# module_RevD.net
KiCad netlist of a schematic drawn in EAGLE
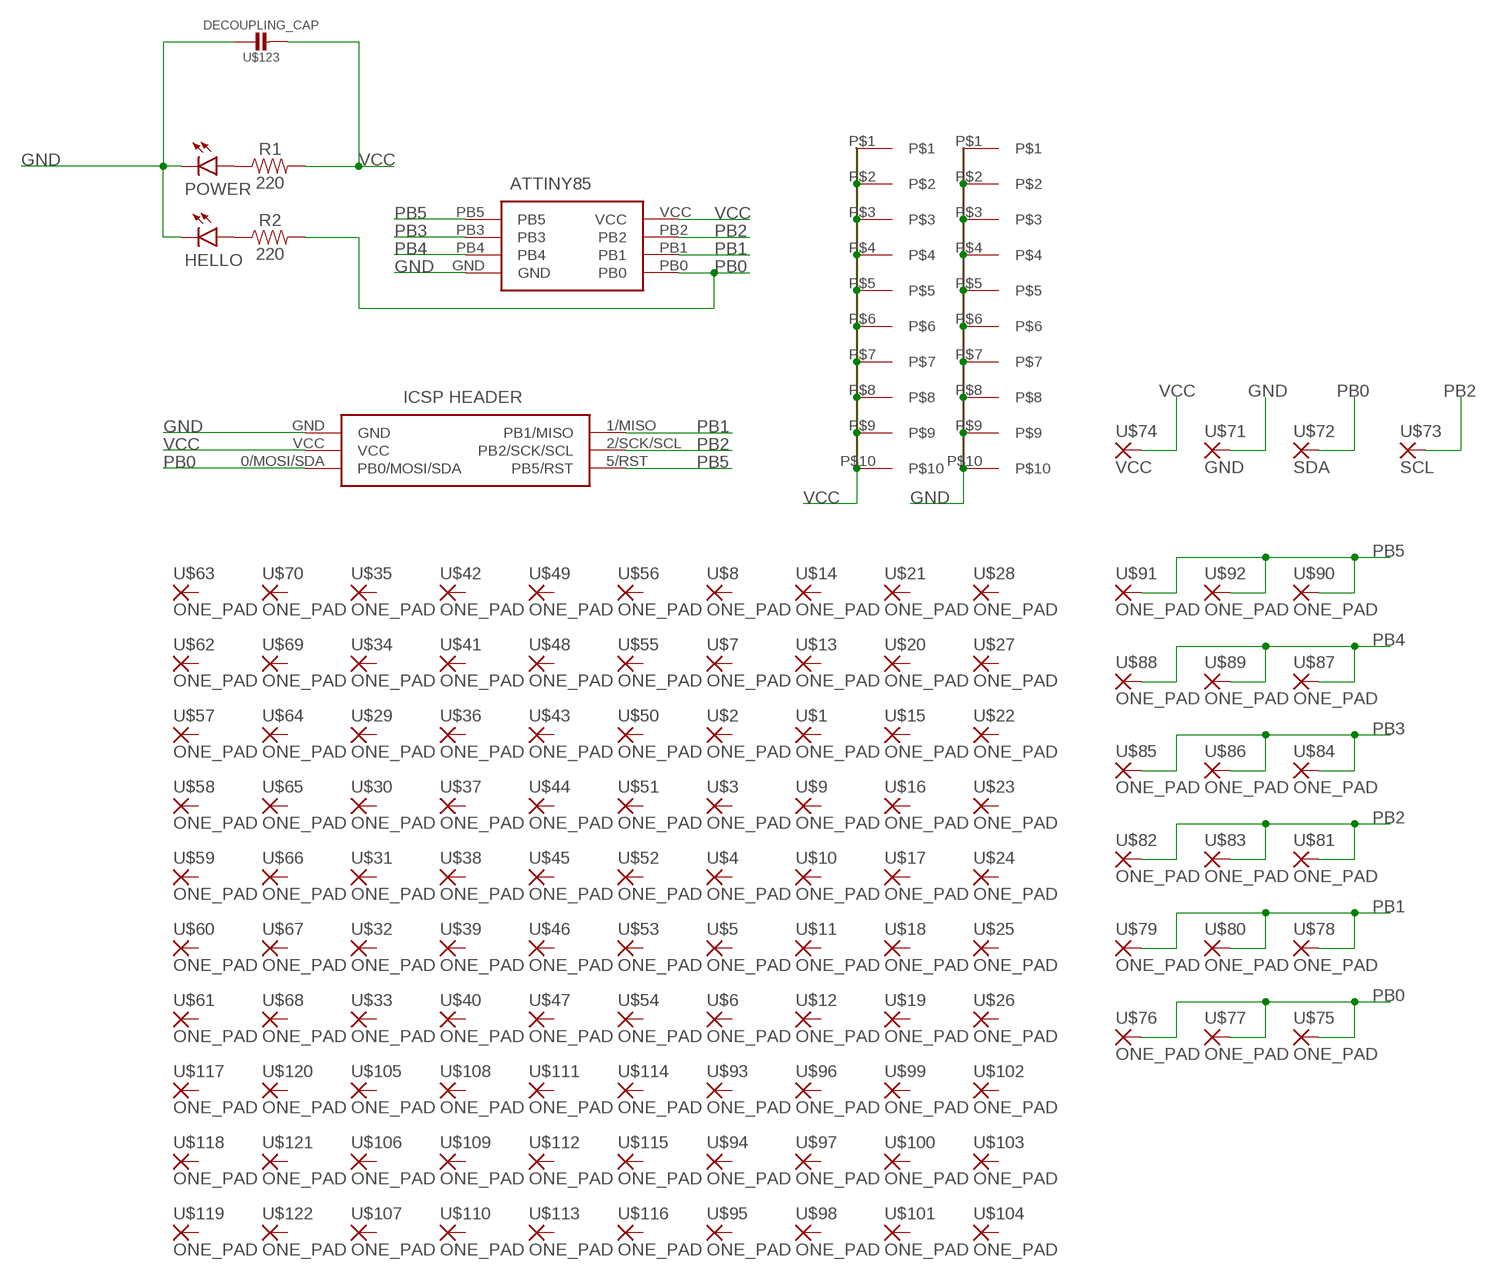
[diagram p0: schematic, sheet 1]

(export (version "E")
  (design (tool "Eeschema 10.0.6"))
  (components
    (comp (ref "GND")
      (value "10X-PADS")
      (footprint "eagle-import:10X-PADS")
      (libsource (lib "eagle-import") (part "10X-PADS"))
    )
    (comp (ref "HELLO")
      (value "LED3MM")
      (footprint "eagle-import:LED3MM")
      (libsource (lib "eagle-import") (part "LED3MM"))
    )
    (comp (ref "IC1")
      (value "ATTINY85-20SU")
      (footprint "eagle-import:SOT127P798X216-8N")
      (fields (field (name "RS_PART_NUMBER") "1331674"))
      (libsource (lib "eagle-import") (part "ATTINY85-20SU"))
    )
    (comp (ref "J1")
      (value "M20-9980346")
      (footprint "eagle-import:HDRV6W64P254_2X3_762X508X868P")
      (fields (field (name "RS_PART_NUMBER") "7457046P"))
      (libsource (lib "eagle-import") (part "M20-9980346"))
    )
    (comp (ref "POWER")
      (value "LED3MM")
      (footprint "eagle-import:LED3MM")
      (libsource (lib "eagle-import") (part "LED3MM"))
    )
    (comp (ref "R1")
      (value "220")
      (footprint "eagle-import:AXIAL-0.3")
      (libsource (lib "eagle-import") (part "RESISTORAXIAL-0.3"))
    )
    (comp (ref "R2")
      (value "220")
      (footprint "eagle-import:AXIAL-0.3")
      (libsource (lib "eagle-import") (part "RESISTORAXIAL-0.3"))
    )
    (comp (ref "U$1")
      (value "ONE_PAD")
      (footprint "eagle-import:1X01")
      (libsource (lib "eagle-import") (part "ONE_PAD"))
    )
    (comp (ref "U$2")
      (value "ONE_PAD")
      (footprint "eagle-import:1X01")
      (libsource (lib "eagle-import") (part "ONE_PAD"))
    )
    (comp (ref "U$3")
      (value "ONE_PAD")
      (footprint "eagle-import:1X01")
      (libsource (lib "eagle-import") (part "ONE_PAD"))
    )
    (comp (ref "U$4")
      (value "ONE_PAD")
      (footprint "eagle-import:1X01")
      (libsource (lib "eagle-import") (part "ONE_PAD"))
    )
    (comp (ref "U$5")
      (value "ONE_PAD")
      (footprint "eagle-import:1X01")
      (libsource (lib "eagle-import") (part "ONE_PAD"))
    )
    (comp (ref "U$6")
      (value "ONE_PAD")
      (footprint "eagle-import:1X01")
      (libsource (lib "eagle-import") (part "ONE_PAD"))
    )
    (comp (ref "U$7")
      (value "ONE_PAD")
      (footprint "eagle-import:1X01")
      (libsource (lib "eagle-import") (part "ONE_PAD"))
    )
    (comp (ref "U$8")
      (value "ONE_PAD")
      (footprint "eagle-import:1X01")
      (libsource (lib "eagle-import") (part "ONE_PAD"))
    )
    (comp (ref "U$9")
      (value "ONE_PAD")
      (footprint "eagle-import:1X01")
      (libsource (lib "eagle-import") (part "ONE_PAD"))
    )
    (comp (ref "U$10")
      (value "ONE_PAD")
      (footprint "eagle-import:1X01")
      (libsource (lib "eagle-import") (part "ONE_PAD"))
    )
    (comp (ref "U$11")
      (value "ONE_PAD")
      (footprint "eagle-import:1X01")
      (libsource (lib "eagle-import") (part "ONE_PAD"))
    )
    (comp (ref "U$12")
      (value "ONE_PAD")
      (footprint "eagle-import:1X01")
      (libsource (lib "eagle-import") (part "ONE_PAD"))
    )
    (comp (ref "U$13")
      (value "ONE_PAD")
      (footprint "eagle-import:1X01")
      (libsource (lib "eagle-import") (part "ONE_PAD"))
    )
    (comp (ref "U$14")
      (value "ONE_PAD")
      (footprint "eagle-import:1X01")
      (libsource (lib "eagle-import") (part "ONE_PAD"))
    )
    (comp (ref "U$15")
      (value "ONE_PAD")
      (footprint "eagle-import:1X01")
      (libsource (lib "eagle-import") (part "ONE_PAD"))
    )
    (comp (ref "U$16")
      (value "ONE_PAD")
      (footprint "eagle-import:1X01")
      (libsource (lib "eagle-import") (part "ONE_PAD"))
    )
    (comp (ref "U$17")
      (value "ONE_PAD")
      (footprint "eagle-import:1X01")
      (libsource (lib "eagle-import") (part "ONE_PAD"))
    )
    (comp (ref "U$18")
      (value "ONE_PAD")
      (footprint "eagle-import:1X01")
      (libsource (lib "eagle-import") (part "ONE_PAD"))
    )
    (comp (ref "U$19")
      (value "ONE_PAD")
      (footprint "eagle-import:1X01")
      (libsource (lib "eagle-import") (part "ONE_PAD"))
    )
    (comp (ref "U$20")
      (value "ONE_PAD")
      (footprint "eagle-import:1X01")
      (libsource (lib "eagle-import") (part "ONE_PAD"))
    )
    (comp (ref "U$21")
      (value "ONE_PAD")
      (footprint "eagle-import:1X01")
      (libsource (lib "eagle-import") (part "ONE_PAD"))
    )
    (comp (ref "U$22")
      (value "ONE_PAD")
      (footprint "eagle-import:1X01")
      (libsource (lib "eagle-import") (part "ONE_PAD"))
    )
    (comp (ref "U$23")
      (value "ONE_PAD")
      (footprint "eagle-import:1X01")
      (libsource (lib "eagle-import") (part "ONE_PAD"))
    )
    (comp (ref "U$24")
      (value "ONE_PAD")
      (footprint "eagle-import:1X01")
      (libsource (lib "eagle-import") (part "ONE_PAD"))
    )
    (comp (ref "U$25")
      (value "ONE_PAD")
      (footprint "eagle-import:1X01")
      (libsource (lib "eagle-import") (part "ONE_PAD"))
    )
    (comp (ref "U$26")
      (value "ONE_PAD")
      (footprint "eagle-import:1X01")
      (libsource (lib "eagle-import") (part "ONE_PAD"))
    )
    (comp (ref "U$27")
      (value "ONE_PAD")
      (footprint "eagle-import:1X01")
      (libsource (lib "eagle-import") (part "ONE_PAD"))
    )
    (comp (ref "U$28")
      (value "ONE_PAD")
      (footprint "eagle-import:1X01")
      (libsource (lib "eagle-import") (part "ONE_PAD"))
    )
    (comp (ref "U$29")
      (value "ONE_PAD")
      (footprint "eagle-import:1X01")
      (libsource (lib "eagle-import") (part "ONE_PAD"))
    )
    (comp (ref "U$30")
      (value "ONE_PAD")
      (footprint "eagle-import:1X01")
      (libsource (lib "eagle-import") (part "ONE_PAD"))
    )
    (comp (ref "U$31")
      (value "ONE_PAD")
      (footprint "eagle-import:1X01")
      (libsource (lib "eagle-import") (part "ONE_PAD"))
    )
    (comp (ref "U$32")
      (value "ONE_PAD")
      (footprint "eagle-import:1X01")
      (libsource (lib "eagle-import") (part "ONE_PAD"))
    )
    (comp (ref "U$33")
      (value "ONE_PAD")
      (footprint "eagle-import:1X01")
      (libsource (lib "eagle-import") (part "ONE_PAD"))
    )
    (comp (ref "U$34")
      (value "ONE_PAD")
      (footprint "eagle-import:1X01")
      (libsource (lib "eagle-import") (part "ONE_PAD"))
    )
    (comp (ref "U$35")
      (value "ONE_PAD")
      (footprint "eagle-import:1X01")
      (libsource (lib "eagle-import") (part "ONE_PAD"))
    )
    (comp (ref "U$36")
      (value "ONE_PAD")
      (footprint "eagle-import:1X01")
      (libsource (lib "eagle-import") (part "ONE_PAD"))
    )
    (comp (ref "U$37")
      (value "ONE_PAD")
      (footprint "eagle-import:1X01")
      (libsource (lib "eagle-import") (part "ONE_PAD"))
    )
    (comp (ref "U$38")
      (value "ONE_PAD")
      (footprint "eagle-import:1X01")
      (libsource (lib "eagle-import") (part "ONE_PAD"))
    )
    (comp (ref "U$39")
      (value "ONE_PAD")
      (footprint "eagle-import:1X01")
      (libsource (lib "eagle-import") (part "ONE_PAD"))
    )
    (comp (ref "U$40")
      (value "ONE_PAD")
      (footprint "eagle-import:1X01")
      (libsource (lib "eagle-import") (part "ONE_PAD"))
    )
    (comp (ref "U$41")
      (value "ONE_PAD")
      (footprint "eagle-import:1X01")
      (libsource (lib "eagle-import") (part "ONE_PAD"))
    )
    (comp (ref "U$42")
      (value "ONE_PAD")
      (footprint "eagle-import:1X01")
      (libsource (lib "eagle-import") (part "ONE_PAD"))
    )
    (comp (ref "U$43")
      (value "ONE_PAD")
      (footprint "eagle-import:1X01")
      (libsource (lib "eagle-import") (part "ONE_PAD"))
    )
    (comp (ref "U$44")
      (value "ONE_PAD")
      (footprint "eagle-import:1X01")
      (libsource (lib "eagle-import") (part "ONE_PAD"))
    )
    (comp (ref "U$45")
      (value "ONE_PAD")
      (footprint "eagle-import:1X01")
      (libsource (lib "eagle-import") (part "ONE_PAD"))
    )
    (comp (ref "U$46")
      (value "ONE_PAD")
      (footprint "eagle-import:1X01")
      (libsource (lib "eagle-import") (part "ONE_PAD"))
    )
    (comp (ref "U$47")
      (value "ONE_PAD")
      (footprint "eagle-import:1X01")
      (libsource (lib "eagle-import") (part "ONE_PAD"))
    )
    (comp (ref "U$48")
      (value "ONE_PAD")
      (footprint "eagle-import:1X01")
      (libsource (lib "eagle-import") (part "ONE_PAD"))
    )
    (comp (ref "U$49")
      (value "ONE_PAD")
      (footprint "eagle-import:1X01")
      (libsource (lib "eagle-import") (part "ONE_PAD"))
    )
    (comp (ref "U$50")
      (value "ONE_PAD")
      (footprint "eagle-import:1X01")
      (libsource (lib "eagle-import") (part "ONE_PAD"))
    )
    (comp (ref "U$51")
      (value "ONE_PAD")
      (footprint "eagle-import:1X01")
      (libsource (lib "eagle-import") (part "ONE_PAD"))
    )
    (comp (ref "U$52")
      (value "ONE_PAD")
      (footprint "eagle-import:1X01")
      (libsource (lib "eagle-import") (part "ONE_PAD"))
    )
    (comp (ref "U$53")
      (value "ONE_PAD")
      (footprint "eagle-import:1X01")
      (libsource (lib "eagle-import") (part "ONE_PAD"))
    )
    (comp (ref "U$54")
      (value "ONE_PAD")
      (footprint "eagle-import:1X01")
      (libsource (lib "eagle-import") (part "ONE_PAD"))
    )
    (comp (ref "U$55")
      (value "ONE_PAD")
      (footprint "eagle-import:1X01")
      (libsource (lib "eagle-import") (part "ONE_PAD"))
    )
    (comp (ref "U$56")
      (value "ONE_PAD")
      (footprint "eagle-import:1X01")
      (libsource (lib "eagle-import") (part "ONE_PAD"))
    )
    (comp (ref "U$57")
      (value "ONE_PAD")
      (footprint "eagle-import:1X01")
      (libsource (lib "eagle-import") (part "ONE_PAD"))
    )
    (comp (ref "U$58")
      (value "ONE_PAD")
      (footprint "eagle-import:1X01")
      (libsource (lib "eagle-import") (part "ONE_PAD"))
    )
    (comp (ref "U$59")
      (value "ONE_PAD")
      (footprint "eagle-import:1X01")
      (libsource (lib "eagle-import") (part "ONE_PAD"))
    )
    (comp (ref "U$60")
      (value "ONE_PAD")
      (footprint "eagle-import:1X01")
      (libsource (lib "eagle-import") (part "ONE_PAD"))
    )
    (comp (ref "U$61")
      (value "ONE_PAD")
      (footprint "eagle-import:1X01")
      (libsource (lib "eagle-import") (part "ONE_PAD"))
    )
    (comp (ref "U$62")
      (value "ONE_PAD")
      (footprint "eagle-import:1X01")
      (libsource (lib "eagle-import") (part "ONE_PAD"))
    )
    (comp (ref "U$63")
      (value "ONE_PAD")
      (footprint "eagle-import:1X01")
      (libsource (lib "eagle-import") (part "ONE_PAD"))
    )
    (comp (ref "U$64")
      (value "ONE_PAD")
      (footprint "eagle-import:1X01")
      (libsource (lib "eagle-import") (part "ONE_PAD"))
    )
    (comp (ref "U$65")
      (value "ONE_PAD")
      (footprint "eagle-import:1X01")
      (libsource (lib "eagle-import") (part "ONE_PAD"))
    )
    (comp (ref "U$66")
      (value "ONE_PAD")
      (footprint "eagle-import:1X01")
      (libsource (lib "eagle-import") (part "ONE_PAD"))
    )
    (comp (ref "U$67")
      (value "ONE_PAD")
      (footprint "eagle-import:1X01")
      (libsource (lib "eagle-import") (part "ONE_PAD"))
    )
    (comp (ref "U$68")
      (value "ONE_PAD")
      (footprint "eagle-import:1X01")
      (libsource (lib "eagle-import") (part "ONE_PAD"))
    )
    (comp (ref "U$69")
      (value "ONE_PAD")
      (footprint "eagle-import:1X01")
      (libsource (lib "eagle-import") (part "ONE_PAD"))
    )
    (comp (ref "U$70")
      (value "ONE_PAD")
      (footprint "eagle-import:1X01")
      (libsource (lib "eagle-import") (part "ONE_PAD"))
    )
    (comp (ref "U$71")
      (value "GND")
      (footprint "eagle-import:1X01")
      (libsource (lib "eagle-import") (part "ONE_PAD"))
    )
    (comp (ref "U$72")
      (value "SDA")
      (footprint "eagle-import:1X01")
      (libsource (lib "eagle-import") (part "ONE_PAD"))
    )
    (comp (ref "U$73")
      (value "SCL")
      (footprint "eagle-import:1X01")
      (libsource (lib "eagle-import") (part "ONE_PAD"))
    )
    (comp (ref "U$74")
      (value "VCC")
      (footprint "eagle-import:1X01")
      (libsource (lib "eagle-import") (part "ONE_PAD"))
    )
    (comp (ref "U$75")
      (value "ONE_PAD")
      (footprint "eagle-import:1X01")
      (libsource (lib "eagle-import") (part "ONE_PAD"))
    )
    (comp (ref "U$76")
      (value "ONE_PAD")
      (footprint "eagle-import:1X01")
      (libsource (lib "eagle-import") (part "ONE_PAD"))
    )
    (comp (ref "U$77")
      (value "ONE_PAD")
      (footprint "eagle-import:1X01")
      (libsource (lib "eagle-import") (part "ONE_PAD"))
    )
    (comp (ref "U$78")
      (value "ONE_PAD")
      (footprint "eagle-import:1X01")
      (libsource (lib "eagle-import") (part "ONE_PAD"))
    )
    (comp (ref "U$79")
      (value "ONE_PAD")
      (footprint "eagle-import:1X01")
      (libsource (lib "eagle-import") (part "ONE_PAD"))
    )
    (comp (ref "U$80")
      (value "ONE_PAD")
      (footprint "eagle-import:1X01")
      (libsource (lib "eagle-import") (part "ONE_PAD"))
    )
    (comp (ref "U$81")
      (value "ONE_PAD")
      (footprint "eagle-import:1X01")
      (libsource (lib "eagle-import") (part "ONE_PAD"))
    )
    (comp (ref "U$82")
      (value "ONE_PAD")
      (footprint "eagle-import:1X01")
      (libsource (lib "eagle-import") (part "ONE_PAD"))
    )
    (comp (ref "U$83")
      (value "ONE_PAD")
      (footprint "eagle-import:1X01")
      (libsource (lib "eagle-import") (part "ONE_PAD"))
    )
    (comp (ref "U$84")
      (value "ONE_PAD")
      (footprint "eagle-import:1X01")
      (libsource (lib "eagle-import") (part "ONE_PAD"))
    )
    (comp (ref "U$85")
      (value "ONE_PAD")
      (footprint "eagle-import:1X01")
      (libsource (lib "eagle-import") (part "ONE_PAD"))
    )
    (comp (ref "U$86")
      (value "ONE_PAD")
      (footprint "eagle-import:1X01")
      (libsource (lib "eagle-import") (part "ONE_PAD"))
    )
    (comp (ref "U$87")
      (value "ONE_PAD")
      (footprint "eagle-import:1X01")
      (libsource (lib "eagle-import") (part "ONE_PAD"))
    )
    (comp (ref "U$88")
      (value "ONE_PAD")
      (footprint "eagle-import:1X01")
      (libsource (lib "eagle-import") (part "ONE_PAD"))
    )
    (comp (ref "U$89")
      (value "ONE_PAD")
      (footprint "eagle-import:1X01")
      (libsource (lib "eagle-import") (part "ONE_PAD"))
    )
    (comp (ref "U$90")
      (value "ONE_PAD")
      (footprint "eagle-import:1X01")
      (libsource (lib "eagle-import") (part "ONE_PAD"))
    )
    (comp (ref "U$91")
      (value "ONE_PAD")
      (footprint "eagle-import:1X01")
      (libsource (lib "eagle-import") (part "ONE_PAD"))
    )
    (comp (ref "U$92")
      (value "ONE_PAD")
      (footprint "eagle-import:1X01")
      (libsource (lib "eagle-import") (part "ONE_PAD"))
    )
    (comp (ref "U$93")
      (value "ONE_PAD")
      (footprint "eagle-import:1X01")
      (libsource (lib "eagle-import") (part "ONE_PAD"))
    )
    (comp (ref "U$94")
      (value "ONE_PAD")
      (footprint "eagle-import:1X01")
      (libsource (lib "eagle-import") (part "ONE_PAD"))
    )
    (comp (ref "U$95")
      (value "ONE_PAD")
      (footprint "eagle-import:1X01")
      (libsource (lib "eagle-import") (part "ONE_PAD"))
    )
    (comp (ref "U$96")
      (value "ONE_PAD")
      (footprint "eagle-import:1X01")
      (libsource (lib "eagle-import") (part "ONE_PAD"))
    )
    (comp (ref "U$97")
      (value "ONE_PAD")
      (footprint "eagle-import:1X01")
      (libsource (lib "eagle-import") (part "ONE_PAD"))
    )
    (comp (ref "U$98")
      (value "ONE_PAD")
      (footprint "eagle-import:1X01")
      (libsource (lib "eagle-import") (part "ONE_PAD"))
    )
    (comp (ref "U$99")
      (value "ONE_PAD")
      (footprint "eagle-import:1X01")
      (libsource (lib "eagle-import") (part "ONE_PAD"))
    )
    (comp (ref "U$100")
      (value "ONE_PAD")
      (footprint "eagle-import:1X01")
      (libsource (lib "eagle-import") (part "ONE_PAD"))
    )
    (comp (ref "U$101")
      (value "ONE_PAD")
      (footprint "eagle-import:1X01")
      (libsource (lib "eagle-import") (part "ONE_PAD"))
    )
    (comp (ref "U$102")
      (value "ONE_PAD")
      (footprint "eagle-import:1X01")
      (libsource (lib "eagle-import") (part "ONE_PAD"))
    )
    (comp (ref "U$103")
      (value "ONE_PAD")
      (footprint "eagle-import:1X01")
      (libsource (lib "eagle-import") (part "ONE_PAD"))
    )
    (comp (ref "U$104")
      (value "ONE_PAD")
      (footprint "eagle-import:1X01")
      (libsource (lib "eagle-import") (part "ONE_PAD"))
    )
    (comp (ref "U$105")
      (value "ONE_PAD")
      (footprint "eagle-import:1X01")
      (libsource (lib "eagle-import") (part "ONE_PAD"))
    )
    (comp (ref "U$106")
      (value "ONE_PAD")
      (footprint "eagle-import:1X01")
      (libsource (lib "eagle-import") (part "ONE_PAD"))
    )
    (comp (ref "U$107")
      (value "ONE_PAD")
      (footprint "eagle-import:1X01")
      (libsource (lib "eagle-import") (part "ONE_PAD"))
    )
    (comp (ref "U$108")
      (value "ONE_PAD")
      (footprint "eagle-import:1X01")
      (libsource (lib "eagle-import") (part "ONE_PAD"))
    )
    (comp (ref "U$109")
      (value "ONE_PAD")
      (footprint "eagle-import:1X01")
      (libsource (lib "eagle-import") (part "ONE_PAD"))
    )
    (comp (ref "U$110")
      (value "ONE_PAD")
      (footprint "eagle-import:1X01")
      (libsource (lib "eagle-import") (part "ONE_PAD"))
    )
    (comp (ref "U$111")
      (value "ONE_PAD")
      (footprint "eagle-import:1X01")
      (libsource (lib "eagle-import") (part "ONE_PAD"))
    )
    (comp (ref "U$112")
      (value "ONE_PAD")
      (footprint "eagle-import:1X01")
      (libsource (lib "eagle-import") (part "ONE_PAD"))
    )
    (comp (ref "U$113")
      (value "ONE_PAD")
      (footprint "eagle-import:1X01")
      (libsource (lib "eagle-import") (part "ONE_PAD"))
    )
    (comp (ref "U$114")
      (value "ONE_PAD")
      (footprint "eagle-import:1X01")
      (libsource (lib "eagle-import") (part "ONE_PAD"))
    )
    (comp (ref "U$115")
      (value "ONE_PAD")
      (footprint "eagle-import:1X01")
      (libsource (lib "eagle-import") (part "ONE_PAD"))
    )
    (comp (ref "U$116")
      (value "ONE_PAD")
      (footprint "eagle-import:1X01")
      (libsource (lib "eagle-import") (part "ONE_PAD"))
    )
    (comp (ref "U$117")
      (value "ONE_PAD")
      (footprint "eagle-import:1X01")
      (libsource (lib "eagle-import") (part "ONE_PAD"))
    )
    (comp (ref "U$118")
      (value "ONE_PAD")
      (footprint "eagle-import:1X01")
      (libsource (lib "eagle-import") (part "ONE_PAD"))
    )
    (comp (ref "U$119")
      (value "ONE_PAD")
      (footprint "eagle-import:1X01")
      (libsource (lib "eagle-import") (part "ONE_PAD"))
    )
    (comp (ref "U$120")
      (value "ONE_PAD")
      (footprint "eagle-import:1X01")
      (libsource (lib "eagle-import") (part "ONE_PAD"))
    )
    (comp (ref "U$121")
      (value "ONE_PAD")
      (footprint "eagle-import:1X01")
      (libsource (lib "eagle-import") (part "ONE_PAD"))
    )
    (comp (ref "U$122")
      (value "ONE_PAD")
      (footprint "eagle-import:1X01")
      (libsource (lib "eagle-import") (part "ONE_PAD"))
    )
    (comp (ref "U$123")
      (value "DECOUPLING_CAP")
      (footprint "eagle-import:DECOUPLING_CAP")
      (libsource (lib "eagle-import") (part "DECOUPLING_CAP"))
    )
    (comp (ref "VCC")
      (value "10X-PADS")
      (footprint "eagle-import:10X-PADS")
      (libsource (lib "eagle-import") (part "10X-PADS"))
    )
  )
  (nets
    (net (code "1") (name "/GND") (class "Default")
      (node (ref "GND") (pin "P$1") (pinfunction "P$1_P$1") (pintype "bidirectional"))
      (node (ref "GND") (pin "P$10") (pinfunction "P$10_P$10") (pintype "bidirectional"))
      (node (ref "GND") (pin "P$2") (pinfunction "P$2_P$2") (pintype "bidirectional"))
      (node (ref "GND") (pin "P$3") (pinfunction "P$3_P$3") (pintype "bidirectional"))
      (node (ref "GND") (pin "P$4") (pinfunction "P$4_P$4") (pintype "bidirectional"))
      (node (ref "GND") (pin "P$5") (pinfunction "P$5_P$5") (pintype "bidirectional"))
      (node (ref "GND") (pin "P$6") (pinfunction "P$6_P$6") (pintype "bidirectional"))
      (node (ref "GND") (pin "P$7") (pinfunction "P$7_P$7") (pintype "bidirectional"))
      (node (ref "GND") (pin "P$8") (pinfunction "P$8_P$8") (pintype "bidirectional"))
      (node (ref "GND") (pin "P$9") (pinfunction "P$9_P$9") (pintype "bidirectional"))
      (node (ref "HELLO") (pin "NEG") (pinfunction "NEG_NEG") (pintype "passive"))
      (node (ref "IC1") (pin "GND") (pinfunction "GND_GND") (pintype "bidirectional"))
      (node (ref "J1") (pin "GND") (pinfunction "GND_GND") (pintype "bidirectional"))
      (node (ref "POWER") (pin "NEG") (pinfunction "NEG_NEG") (pintype "passive"))
      (node (ref "U$123") (pin "1") (pinfunction "1_1") (pintype "passive"))
      (node (ref "U$71") (pin "P$1") (pinfunction "P_P$1") (pintype "passive"))
    )
    (net (code "2") (name "/PB0") (class "Default")
      (node (ref "IC1") (pin "PB0") (pinfunction "PB0_PB0") (pintype "bidirectional"))
      (node (ref "J1") (pin "0/MOSI/SDA") (pinfunction "PB0/MOSI/SDA_0/MOSI/SDA") (pintype "bidirectional"))
      (node (ref "R2") (pin "P$2") (pinfunction "2_P$2") (pintype "passive"))
      (node (ref "U$72") (pin "P$1") (pinfunction "P_P$1") (pintype "passive"))
      (node (ref "U$75") (pin "P$1") (pinfunction "P_P$1") (pintype "passive"))
      (node (ref "U$76") (pin "P$1") (pinfunction "P_P$1") (pintype "passive"))
      (node (ref "U$77") (pin "P$1") (pinfunction "P_P$1") (pintype "passive"))
    )
    (net (code "3") (name "/PB1") (class "Default")
      (node (ref "IC1") (pin "PB1") (pinfunction "PB1_PB1") (pintype "bidirectional"))
      (node (ref "J1") (pin "1/MISO") (pinfunction "PB1/MISO_1/MISO") (pintype "bidirectional"))
      (node (ref "U$78") (pin "P$1") (pinfunction "P_P$1") (pintype "passive"))
      (node (ref "U$79") (pin "P$1") (pinfunction "P_P$1") (pintype "passive"))
      (node (ref "U$80") (pin "P$1") (pinfunction "P_P$1") (pintype "passive"))
    )
    (net (code "4") (name "/PB2") (class "Default")
      (node (ref "IC1") (pin "PB2") (pinfunction "PB2_PB2") (pintype "bidirectional"))
      (node (ref "J1") (pin "2/SCK/SCL") (pinfunction "PB2/SCK/SCL_2/SCK/SCL") (pintype "bidirectional"))
      (node (ref "U$73") (pin "P$1") (pinfunction "P_P$1") (pintype "passive"))
      (node (ref "U$81") (pin "P$1") (pinfunction "P_P$1") (pintype "passive"))
      (node (ref "U$82") (pin "P$1") (pinfunction "P_P$1") (pintype "passive"))
      (node (ref "U$83") (pin "P$1") (pinfunction "P_P$1") (pintype "passive"))
    )
    (net (code "5") (name "/PB3") (class "Default")
      (node (ref "IC1") (pin "PB3") (pinfunction "PB3_PB3") (pintype "bidirectional"))
      (node (ref "U$84") (pin "P$1") (pinfunction "P_P$1") (pintype "passive"))
      (node (ref "U$85") (pin "P$1") (pinfunction "P_P$1") (pintype "passive"))
      (node (ref "U$86") (pin "P$1") (pinfunction "P_P$1") (pintype "passive"))
    )
    (net (code "6") (name "/PB4") (class "Default")
      (node (ref "IC1") (pin "PB4") (pinfunction "PB4_PB4") (pintype "bidirectional"))
      (node (ref "U$87") (pin "P$1") (pinfunction "P_P$1") (pintype "passive"))
      (node (ref "U$88") (pin "P$1") (pinfunction "P_P$1") (pintype "passive"))
      (node (ref "U$89") (pin "P$1") (pinfunction "P_P$1") (pintype "passive"))
    )
    (net (code "7") (name "/PB5") (class "Default")
      (node (ref "IC1") (pin "PB5") (pinfunction "PB5_PB5") (pintype "bidirectional"))
      (node (ref "J1") (pin "5/RST") (pinfunction "PB5/RST_5/RST") (pintype "bidirectional"))
      (node (ref "U$90") (pin "P$1") (pinfunction "P_P$1") (pintype "passive"))
      (node (ref "U$91") (pin "P$1") (pinfunction "P_P$1") (pintype "passive"))
      (node (ref "U$92") (pin "P$1") (pinfunction "P_P$1") (pintype "passive"))
    )
    (net (code "8") (name "/VCC") (class "Default")
      (node (ref "IC1") (pin "VCC") (pinfunction "VCC_VCC") (pintype "bidirectional"))
      (node (ref "J1") (pin "VCC") (pinfunction "VCC_VCC") (pintype "bidirectional"))
      (node (ref "R1") (pin "P$2") (pinfunction "2_P$2") (pintype "passive"))
      (node (ref "U$123") (pin "2") (pinfunction "2_2") (pintype "passive"))
      (node (ref "U$74") (pin "P$1") (pinfunction "P_P$1") (pintype "passive"))
      (node (ref "VCC") (pin "P$1") (pinfunction "P$1_P$1") (pintype "bidirectional"))
      (node (ref "VCC") (pin "P$10") (pinfunction "P$10_P$10") (pintype "bidirectional"))
      (node (ref "VCC") (pin "P$2") (pinfunction "P$2_P$2") (pintype "bidirectional"))
      (node (ref "VCC") (pin "P$3") (pinfunction "P$3_P$3") (pintype "bidirectional"))
      (node (ref "VCC") (pin "P$4") (pinfunction "P$4_P$4") (pintype "bidirectional"))
      (node (ref "VCC") (pin "P$5") (pinfunction "P$5_P$5") (pintype "bidirectional"))
      (node (ref "VCC") (pin "P$6") (pinfunction "P$6_P$6") (pintype "bidirectional"))
      (node (ref "VCC") (pin "P$7") (pinfunction "P$7_P$7") (pintype "bidirectional"))
      (node (ref "VCC") (pin "P$8") (pinfunction "P$8_P$8") (pintype "bidirectional"))
      (node (ref "VCC") (pin "P$9") (pinfunction "P$9_P$9") (pintype "bidirectional"))
    )
    (net (code "9") (name "Net-(R1-1)") (class "Default")
      (node (ref "POWER") (pin "POS") (pinfunction "POS_POS") (pintype "passive"))
      (node (ref "R1") (pin "P$1") (pinfunction "1_P$1") (pintype "passive"))
    )
    (net (code "10") (name "Net-(R2-1)") (class "Default")
      (node (ref "HELLO") (pin "POS") (pinfunction "POS_POS") (pintype "passive"))
      (node (ref "R2") (pin "P$1") (pinfunction "1_P$1") (pintype "passive"))
    )
    (net (code "11") (name "unconnected-(U$1-P-PadP$1)") (class "Default")
      (node (ref "U$1") (pin "P$1") (pinfunction "P_P$1") (pintype "passive"))
    )
    (net (code "12") (name "unconnected-(U$2-P-PadP$1)") (class "Default")
      (node (ref "U$2") (pin "P$1") (pinfunction "P_P$1") (pintype "passive"))
    )
    (net (code "13") (name "unconnected-(U$3-P-PadP$1)") (class "Default")
      (node (ref "U$3") (pin "P$1") (pinfunction "P_P$1") (pintype "passive"))
    )
    (net (code "14") (name "unconnected-(U$4-P-PadP$1)") (class "Default")
      (node (ref "U$4") (pin "P$1") (pinfunction "P_P$1") (pintype "passive"))
    )
    (net (code "15") (name "unconnected-(U$5-P-PadP$1)") (class "Default")
      (node (ref "U$5") (pin "P$1") (pinfunction "P_P$1") (pintype "passive"))
    )
    (net (code "16") (name "unconnected-(U$6-P-PadP$1)") (class "Default")
      (node (ref "U$6") (pin "P$1") (pinfunction "P_P$1") (pintype "passive"))
    )
    (net (code "17") (name "unconnected-(U$7-P-PadP$1)") (class "Default")
      (node (ref "U$7") (pin "P$1") (pinfunction "P_P$1") (pintype "passive"))
    )
    (net (code "18") (name "unconnected-(U$8-P-PadP$1)") (class "Default")
      (node (ref "U$8") (pin "P$1") (pinfunction "P_P$1") (pintype "passive"))
    )
    (net (code "19") (name "unconnected-(U$9-P-PadP$1)") (class "Default")
      (node (ref "U$9") (pin "P$1") (pinfunction "P_P$1") (pintype "passive"))
    )
    (net (code "20") (name "unconnected-(U$10-P-PadP$1)") (class "Default")
      (node (ref "U$10") (pin "P$1") (pinfunction "P_P$1") (pintype "passive"))
    )
    (net (code "21") (name "unconnected-(U$11-P-PadP$1)") (class "Default")
      (node (ref "U$11") (pin "P$1") (pinfunction "P_P$1") (pintype "passive"))
    )
    (net (code "22") (name "unconnected-(U$12-P-PadP$1)") (class "Default")
      (node (ref "U$12") (pin "P$1") (pinfunction "P_P$1") (pintype "passive"))
    )
    (net (code "23") (name "unconnected-(U$13-P-PadP$1)") (class "Default")
      (node (ref "U$13") (pin "P$1") (pinfunction "P_P$1") (pintype "passive"))
    )
    (net (code "24") (name "unconnected-(U$14-P-PadP$1)") (class "Default")
      (node (ref "U$14") (pin "P$1") (pinfunction "P_P$1") (pintype "passive"))
    )
    (net (code "25") (name "unconnected-(U$15-P-PadP$1)") (class "Default")
      (node (ref "U$15") (pin "P$1") (pinfunction "P_P$1") (pintype "passive"))
    )
    (net (code "26") (name "unconnected-(U$16-P-PadP$1)") (class "Default")
      (node (ref "U$16") (pin "P$1") (pinfunction "P_P$1") (pintype "passive"))
    )
    (net (code "27") (name "unconnected-(U$17-P-PadP$1)") (class "Default")
      (node (ref "U$17") (pin "P$1") (pinfunction "P_P$1") (pintype "passive"))
    )
    (net (code "28") (name "unconnected-(U$18-P-PadP$1)") (class "Default")
      (node (ref "U$18") (pin "P$1") (pinfunction "P_P$1") (pintype "passive"))
    )
    (net (code "29") (name "unconnected-(U$19-P-PadP$1)") (class "Default")
      (node (ref "U$19") (pin "P$1") (pinfunction "P_P$1") (pintype "passive"))
    )
    (net (code "30") (name "unconnected-(U$20-P-PadP$1)") (class "Default")
      (node (ref "U$20") (pin "P$1") (pinfunction "P_P$1") (pintype "passive"))
    )
    (net (code "31") (name "unconnected-(U$21-P-PadP$1)") (class "Default")
      (node (ref "U$21") (pin "P$1") (pinfunction "P_P$1") (pintype "passive"))
    )
    (net (code "32") (name "unconnected-(U$22-P-PadP$1)") (class "Default")
      (node (ref "U$22") (pin "P$1") (pinfunction "P_P$1") (pintype "passive"))
    )
    (net (code "33") (name "unconnected-(U$23-P-PadP$1)") (class "Default")
      (node (ref "U$23") (pin "P$1") (pinfunction "P_P$1") (pintype "passive"))
    )
    (net (code "34") (name "unconnected-(U$24-P-PadP$1)") (class "Default")
      (node (ref "U$24") (pin "P$1") (pinfunction "P_P$1") (pintype "passive"))
    )
    (net (code "35") (name "unconnected-(U$25-P-PadP$1)") (class "Default")
      (node (ref "U$25") (pin "P$1") (pinfunction "P_P$1") (pintype "passive"))
    )
    (net (code "36") (name "unconnected-(U$26-P-PadP$1)") (class "Default")
      (node (ref "U$26") (pin "P$1") (pinfunction "P_P$1") (pintype "passive"))
    )
    (net (code "37") (name "unconnected-(U$27-P-PadP$1)") (class "Default")
      (node (ref "U$27") (pin "P$1") (pinfunction "P_P$1") (pintype "passive"))
    )
    (net (code "38") (name "unconnected-(U$28-P-PadP$1)") (class "Default")
      (node (ref "U$28") (pin "P$1") (pinfunction "P_P$1") (pintype "passive"))
    )
    (net (code "39") (name "unconnected-(U$29-P-PadP$1)") (class "Default")
      (node (ref "U$29") (pin "P$1") (pinfunction "P_P$1") (pintype "passive"))
    )
    (net (code "40") (name "unconnected-(U$30-P-PadP$1)") (class "Default")
      (node (ref "U$30") (pin "P$1") (pinfunction "P_P$1") (pintype "passive"))
    )
    (net (code "41") (name "unconnected-(U$31-P-PadP$1)") (class "Default")
      (node (ref "U$31") (pin "P$1") (pinfunction "P_P$1") (pintype "passive"))
    )
    (net (code "42") (name "unconnected-(U$32-P-PadP$1)") (class "Default")
      (node (ref "U$32") (pin "P$1") (pinfunction "P_P$1") (pintype "passive"))
    )
    (net (code "43") (name "unconnected-(U$33-P-PadP$1)") (class "Default")
      (node (ref "U$33") (pin "P$1") (pinfunction "P_P$1") (pintype "passive"))
    )
    (net (code "44") (name "unconnected-(U$34-P-PadP$1)") (class "Default")
      (node (ref "U$34") (pin "P$1") (pinfunction "P_P$1") (pintype "passive"))
    )
    (net (code "45") (name "unconnected-(U$35-P-PadP$1)") (class "Default")
      (node (ref "U$35") (pin "P$1") (pinfunction "P_P$1") (pintype "passive"))
    )
    (net (code "46") (name "unconnected-(U$36-P-PadP$1)") (class "Default")
      (node (ref "U$36") (pin "P$1") (pinfunction "P_P$1") (pintype "passive"))
    )
    (net (code "47") (name "unconnected-(U$37-P-PadP$1)") (class "Default")
      (node (ref "U$37") (pin "P$1") (pinfunction "P_P$1") (pintype "passive"))
    )
    (net (code "48") (name "unconnected-(U$38-P-PadP$1)") (class "Default")
      (node (ref "U$38") (pin "P$1") (pinfunction "P_P$1") (pintype "passive"))
    )
    (net (code "49") (name "unconnected-(U$39-P-PadP$1)") (class "Default")
      (node (ref "U$39") (pin "P$1") (pinfunction "P_P$1") (pintype "passive"))
    )
    (net (code "50") (name "unconnected-(U$40-P-PadP$1)") (class "Default")
      (node (ref "U$40") (pin "P$1") (pinfunction "P_P$1") (pintype "passive"))
    )
    (net (code "51") (name "unconnected-(U$41-P-PadP$1)") (class "Default")
      (node (ref "U$41") (pin "P$1") (pinfunction "P_P$1") (pintype "passive"))
    )
    (net (code "52") (name "unconnected-(U$42-P-PadP$1)") (class "Default")
      (node (ref "U$42") (pin "P$1") (pinfunction "P_P$1") (pintype "passive"))
    )
    (net (code "53") (name "unconnected-(U$43-P-PadP$1)") (class "Default")
      (node (ref "U$43") (pin "P$1") (pinfunction "P_P$1") (pintype "passive"))
    )
    (net (code "54") (name "unconnected-(U$44-P-PadP$1)") (class "Default")
      (node (ref "U$44") (pin "P$1") (pinfunction "P_P$1") (pintype "passive"))
    )
    (net (code "55") (name "unconnected-(U$45-P-PadP$1)") (class "Default")
      (node (ref "U$45") (pin "P$1") (pinfunction "P_P$1") (pintype "passive"))
    )
    (net (code "56") (name "unconnected-(U$46-P-PadP$1)") (class "Default")
      (node (ref "U$46") (pin "P$1") (pinfunction "P_P$1") (pintype "passive"))
    )
    (net (code "57") (name "unconnected-(U$47-P-PadP$1)") (class "Default")
      (node (ref "U$47") (pin "P$1") (pinfunction "P_P$1") (pintype "passive"))
    )
    (net (code "58") (name "unconnected-(U$48-P-PadP$1)") (class "Default")
      (node (ref "U$48") (pin "P$1") (pinfunction "P_P$1") (pintype "passive"))
    )
    (net (code "59") (name "unconnected-(U$49-P-PadP$1)") (class "Default")
      (node (ref "U$49") (pin "P$1") (pinfunction "P_P$1") (pintype "passive"))
    )
    (net (code "60") (name "unconnected-(U$50-P-PadP$1)") (class "Default")
      (node (ref "U$50") (pin "P$1") (pinfunction "P_P$1") (pintype "passive"))
    )
    (net (code "61") (name "unconnected-(U$51-P-PadP$1)") (class "Default")
      (node (ref "U$51") (pin "P$1") (pinfunction "P_P$1") (pintype "passive"))
    )
    (net (code "62") (name "unconnected-(U$52-P-PadP$1)") (class "Default")
      (node (ref "U$52") (pin "P$1") (pinfunction "P_P$1") (pintype "passive"))
    )
    (net (code "63") (name "unconnected-(U$53-P-PadP$1)") (class "Default")
      (node (ref "U$53") (pin "P$1") (pinfunction "P_P$1") (pintype "passive"))
    )
    (net (code "64") (name "unconnected-(U$54-P-PadP$1)") (class "Default")
      (node (ref "U$54") (pin "P$1") (pinfunction "P_P$1") (pintype "passive"))
    )
    (net (code "65") (name "unconnected-(U$55-P-PadP$1)") (class "Default")
      (node (ref "U$55") (pin "P$1") (pinfunction "P_P$1") (pintype "passive"))
    )
    (net (code "66") (name "unconnected-(U$56-P-PadP$1)") (class "Default")
      (node (ref "U$56") (pin "P$1") (pinfunction "P_P$1") (pintype "passive"))
    )
    (net (code "67") (name "unconnected-(U$57-P-PadP$1)") (class "Default")
      (node (ref "U$57") (pin "P$1") (pinfunction "P_P$1") (pintype "passive"))
    )
    (net (code "68") (name "unconnected-(U$58-P-PadP$1)") (class "Default")
      (node (ref "U$58") (pin "P$1") (pinfunction "P_P$1") (pintype "passive"))
    )
    (net (code "69") (name "unconnected-(U$59-P-PadP$1)") (class "Default")
      (node (ref "U$59") (pin "P$1") (pinfunction "P_P$1") (pintype "passive"))
    )
    (net (code "70") (name "unconnected-(U$60-P-PadP$1)") (class "Default")
      (node (ref "U$60") (pin "P$1") (pinfunction "P_P$1") (pintype "passive"))
    )
    (net (code "71") (name "unconnected-(U$61-P-PadP$1)") (class "Default")
      (node (ref "U$61") (pin "P$1") (pinfunction "P_P$1") (pintype "passive"))
    )
    (net (code "72") (name "unconnected-(U$62-P-PadP$1)") (class "Default")
      (node (ref "U$62") (pin "P$1") (pinfunction "P_P$1") (pintype "passive"))
    )
    (net (code "73") (name "unconnected-(U$63-P-PadP$1)") (class "Default")
      (node (ref "U$63") (pin "P$1") (pinfunction "P_P$1") (pintype "passive"))
    )
    (net (code "74") (name "unconnected-(U$64-P-PadP$1)") (class "Default")
      (node (ref "U$64") (pin "P$1") (pinfunction "P_P$1") (pintype "passive"))
    )
    (net (code "75") (name "unconnected-(U$65-P-PadP$1)") (class "Default")
      (node (ref "U$65") (pin "P$1") (pinfunction "P_P$1") (pintype "passive"))
    )
    (net (code "76") (name "unconnected-(U$66-P-PadP$1)") (class "Default")
      (node (ref "U$66") (pin "P$1") (pinfunction "P_P$1") (pintype "passive"))
    )
    (net (code "77") (name "unconnected-(U$67-P-PadP$1)") (class "Default")
      (node (ref "U$67") (pin "P$1") (pinfunction "P_P$1") (pintype "passive"))
    )
    (net (code "78") (name "unconnected-(U$68-P-PadP$1)") (class "Default")
      (node (ref "U$68") (pin "P$1") (pinfunction "P_P$1") (pintype "passive"))
    )
    (net (code "79") (name "unconnected-(U$69-P-PadP$1)") (class "Default")
      (node (ref "U$69") (pin "P$1") (pinfunction "P_P$1") (pintype "passive"))
    )
    (net (code "80") (name "unconnected-(U$70-P-PadP$1)") (class "Default")
      (node (ref "U$70") (pin "P$1") (pinfunction "P_P$1") (pintype "passive"))
    )
    (net (code "81") (name "unconnected-(U$93-P-PadP$1)") (class "Default")
      (node (ref "U$93") (pin "P$1") (pinfunction "P_P$1") (pintype "passive"))
    )
    (net (code "82") (name "unconnected-(U$94-P-PadP$1)") (class "Default")
      (node (ref "U$94") (pin "P$1") (pinfunction "P_P$1") (pintype "passive"))
    )
    (net (code "83") (name "unconnected-(U$95-P-PadP$1)") (class "Default")
      (node (ref "U$95") (pin "P$1") (pinfunction "P_P$1") (pintype "passive"))
    )
    (net (code "84") (name "unconnected-(U$96-P-PadP$1)") (class "Default")
      (node (ref "U$96") (pin "P$1") (pinfunction "P_P$1") (pintype "passive"))
    )
    (net (code "85") (name "unconnected-(U$97-P-PadP$1)") (class "Default")
      (node (ref "U$97") (pin "P$1") (pinfunction "P_P$1") (pintype "passive"))
    )
    (net (code "86") (name "unconnected-(U$98-P-PadP$1)") (class "Default")
      (node (ref "U$98") (pin "P$1") (pinfunction "P_P$1") (pintype "passive"))
    )
    (net (code "87") (name "unconnected-(U$99-P-PadP$1)") (class "Default")
      (node (ref "U$99") (pin "P$1") (pinfunction "P_P$1") (pintype "passive"))
    )
    (net (code "88") (name "unconnected-(U$100-P-PadP$1)") (class "Default")
      (node (ref "U$100") (pin "P$1") (pinfunction "P_P$1") (pintype "passive"))
    )
    (net (code "89") (name "unconnected-(U$101-P-PadP$1)") (class "Default")
      (node (ref "U$101") (pin "P$1") (pinfunction "P_P$1") (pintype "passive"))
    )
    (net (code "90") (name "unconnected-(U$102-P-PadP$1)") (class "Default")
      (node (ref "U$102") (pin "P$1") (pinfunction "P_P$1") (pintype "passive"))
    )
    (net (code "91") (name "unconnected-(U$103-P-PadP$1)") (class "Default")
      (node (ref "U$103") (pin "P$1") (pinfunction "P_P$1") (pintype "passive"))
    )
    (net (code "92") (name "unconnected-(U$104-P-PadP$1)") (class "Default")
      (node (ref "U$104") (pin "P$1") (pinfunction "P_P$1") (pintype "passive"))
    )
    (net (code "93") (name "unconnected-(U$105-P-PadP$1)") (class "Default")
      (node (ref "U$105") (pin "P$1") (pinfunction "P_P$1") (pintype "passive"))
    )
    (net (code "94") (name "unconnected-(U$106-P-PadP$1)") (class "Default")
      (node (ref "U$106") (pin "P$1") (pinfunction "P_P$1") (pintype "passive"))
    )
    (net (code "95") (name "unconnected-(U$107-P-PadP$1)") (class "Default")
      (node (ref "U$107") (pin "P$1") (pinfunction "P_P$1") (pintype "passive"))
    )
    (net (code "96") (name "unconnected-(U$108-P-PadP$1)") (class "Default")
      (node (ref "U$108") (pin "P$1") (pinfunction "P_P$1") (pintype "passive"))
    )
    (net (code "97") (name "unconnected-(U$109-P-PadP$1)") (class "Default")
      (node (ref "U$109") (pin "P$1") (pinfunction "P_P$1") (pintype "passive"))
    )
    (net (code "98") (name "unconnected-(U$110-P-PadP$1)") (class "Default")
      (node (ref "U$110") (pin "P$1") (pinfunction "P_P$1") (pintype "passive"))
    )
    (net (code "99") (name "unconnected-(U$111-P-PadP$1)") (class "Default")
      (node (ref "U$111") (pin "P$1") (pinfunction "P_P$1") (pintype "passive"))
    )
    (net (code "100") (name "unconnected-(U$112-P-PadP$1)") (class "Default")
      (node (ref "U$112") (pin "P$1") (pinfunction "P_P$1") (pintype "passive"))
    )
    (net (code "101") (name "unconnected-(U$113-P-PadP$1)") (class "Default")
      (node (ref "U$113") (pin "P$1") (pinfunction "P_P$1") (pintype "passive"))
    )
    (net (code "102") (name "unconnected-(U$114-P-PadP$1)") (class "Default")
      (node (ref "U$114") (pin "P$1") (pinfunction "P_P$1") (pintype "passive"))
    )
    (net (code "103") (name "unconnected-(U$115-P-PadP$1)") (class "Default")
      (node (ref "U$115") (pin "P$1") (pinfunction "P_P$1") (pintype "passive"))
    )
    (net (code "104") (name "unconnected-(U$116-P-PadP$1)") (class "Default")
      (node (ref "U$116") (pin "P$1") (pinfunction "P_P$1") (pintype "passive"))
    )
    (net (code "105") (name "unconnected-(U$117-P-PadP$1)") (class "Default")
      (node (ref "U$117") (pin "P$1") (pinfunction "P_P$1") (pintype "passive"))
    )
    (net (code "106") (name "unconnected-(U$118-P-PadP$1)") (class "Default")
      (node (ref "U$118") (pin "P$1") (pinfunction "P_P$1") (pintype "passive"))
    )
    (net (code "107") (name "unconnected-(U$119-P-PadP$1)") (class "Default")
      (node (ref "U$119") (pin "P$1") (pinfunction "P_P$1") (pintype "passive"))
    )
    (net (code "108") (name "unconnected-(U$120-P-PadP$1)") (class "Default")
      (node (ref "U$120") (pin "P$1") (pinfunction "P_P$1") (pintype "passive"))
    )
    (net (code "109") (name "unconnected-(U$121-P-PadP$1)") (class "Default")
      (node (ref "U$121") (pin "P$1") (pinfunction "P_P$1") (pintype "passive"))
    )
    (net (code "110") (name "unconnected-(U$122-P-PadP$1)") (class "Default")
      (node (ref "U$122") (pin "P$1") (pinfunction "P_P$1") (pintype "passive"))
    )
  )
)
